# POWER2.net
KiCad netlist of a schematic drawn in Altium Designer
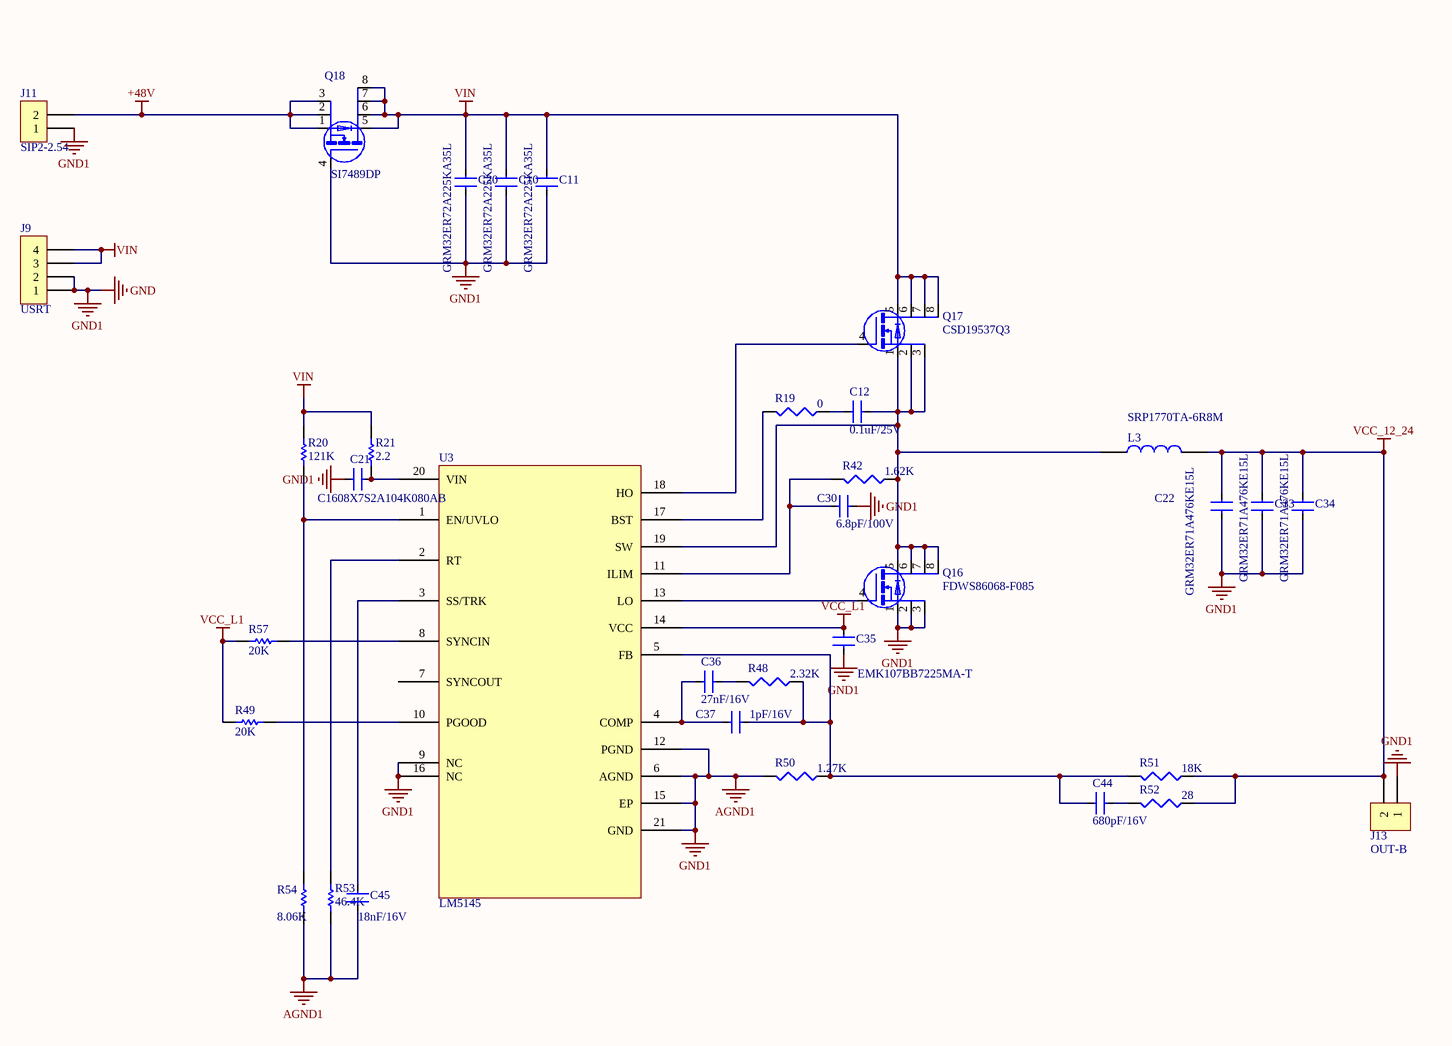
[diagram p0: POWER2.SchDoc]

(export (version "E")
  (design (tool "Eeschema 10.0.6"))
  (components
    (comp (ref "C10")
      (value "GRM32ER72A225KA35L")
      (footprint "1210C")
      (description "CCX85-103")
      (libsource (lib "无极性电容") (part "0.01UF"))
    )
    (comp (ref "C11")
      (value "GRM32ER72A225KA35L")
      (footprint "1210C")
      (description "CCX85-103")
      (libsource (lib "无极性电容") (part "0.01UF"))
    )
    (comp (ref "C12")
      (value "0.1uF/25V")
      (footprint "0603C")
      (description "CCX85-103")
      (libsource (lib "无极性电容") (part "0.01UF"))
    )
    (comp (ref "C20")
      (value "GRM32ER72A225KA35L")
      (footprint "1210C")
      (description "CCX85-103")
      (libsource (lib "无极性电容") (part "0.01UF"))
    )
    (comp (ref "C21")
      (value "C1608X7S2A104K080AB")
      (footprint "0603C")
      (description "CCX85-103")
      (libsource (lib "无极性电容") (part "0.01UF"))
    )
    (comp (ref "C22")
      (value "GRM32ER71A476KE15L")
      (footprint "1210C")
      (description "CCX85-103")
      (libsource (lib "无极性电容") (part "0.01UF"))
    )
    (comp (ref "C30")
      (value "6.8pF/100V")
      (footprint "0603C")
      (description "CCX85-103")
      (libsource (lib "无极性电容") (part "0.01UF"))
    )
    (comp (ref "C33")
      (value "GRM32ER71A476KE15L")
      (footprint "1210C")
      (description "CCX85-103")
      (libsource (lib "无极性电容") (part "0.01UF"))
    )
    (comp (ref "C34")
      (value "GRM32ER71A476KE15L")
      (footprint "1210C")
      (description "CCX85-103")
      (libsource (lib "无极性电容") (part "0.01UF"))
    )
    (comp (ref "C35")
      (value "EMK107BB7225MA-T")
      (footprint "0603C")
      (description "CCX85-103")
      (libsource (lib "无极性电容") (part "0.01UF"))
    )
    (comp (ref "C36")
      (value "27nF/16V")
      (footprint "0603C")
      (description "CCX85-103")
      (libsource (lib "无极性电容") (part "0.01UF"))
    )
    (comp (ref "C37")
      (value "1pF/16V")
      (footprint "0603C")
      (description "CCX85-103")
      (libsource (lib "无极性电容") (part "0.01UF"))
    )
    (comp (ref "C44")
      (value "680pF/16V")
      (footprint "0603C")
      (description "CCX85-103")
      (libsource (lib "无极性电容") (part "0.01UF"))
    )
    (comp (ref "C45")
      (value "18nF/16V")
      (footprint "0603C")
      (description "CCX85-103")
      (libsource (lib "无极性电容") (part "0.01UF"))
    )
    (comp (ref "J9")
      (value "USRT")
      (footprint "SIP-4L")
      (description "CN-SIP4-2.54")
      (libsource (lib "接插件") (part "SIP4-2.54"))
    )
    (comp (ref "J11")
      (value "SIP2-2.54")
      (footprint "CH3.96-2P")
      (description "CN-SIP2-2.54")
      (libsource (lib "接插件") (part "SIP2-2.54"))
    )
    (comp (ref "J13")
      (value "OUT-B")
      (footprint "CH3.96-2P")
      (description "Connector")
      (libsource (lib "SM") (part "CON2"))
    )
    (comp (ref "L3")
      (value "SRP1770TA-6R8M")
      (footprint "SRP1270-2R2M")
      (libsource (lib "*") (part "INDUCTOR"))
    )
    (comp (ref "Q16")
      (value "FDWS86068-F085")
      (footprint "PowerPAK SO-8")
      (description "Si4004DY")
      (libsource (lib "Schlib_20110825") (part "Si4004DY"))
    )
    (comp (ref "Q17")
      (value "CSD19537Q3")
      (footprint "PowerPAK SO-8")
      (description "Si4004DY")
      (libsource (lib "Schlib_20110825") (part "Si4004DY"))
    )
    (comp (ref "Q18")
      (value "SI7489DP")
      (footprint "PowerPAK SO-8")
      (description "Si4004DY")
      (libsource (lib "") (part "Si4004DY_1"))
    )
    (comp (ref "R19")
      (value "0")
      (footprint "0603R")
      (description "Resistor")
      (fields (field (name "PUBLISHER") "Altium Limited"))
      (libsource (lib "SM") (part "Res3"))
    )
    (comp (ref "R20")
      (value "121K")
      (footprint "0805R")
      (description "Semiconductor Resistor")
      (fields (field (name "PUBLISHER") "Altium Limited"))
      (libsource (lib "Miscellaneous Devices") (part "Res Semi"))
    )
    (comp (ref "R21")
      (value "2.2")
      (footprint "0603R")
      (description "Semiconductor Resistor")
      (fields (field (name "PUBLISHER") "Altium Limited"))
      (libsource (lib "Miscellaneous Devices") (part "Res Semi"))
    )
    (comp (ref "R42")
      (value "1.62K")
      (footprint "0603R")
      (description "Resistor")
      (fields (field (name "PUBLISHER") "Altium Limited"))
      (libsource (lib "SM") (part "Res3"))
    )
    (comp (ref "R48")
      (value "2.32K")
      (footprint "0603R")
      (description "Resistor")
      (fields (field (name "PUBLISHER") "Altium Limited"))
      (libsource (lib "SM") (part "Res3"))
    )
    (comp (ref "R49")
      (value "20K")
      (footprint "0603R")
      (description "Semiconductor Resistor")
      (fields (field (name "PUBLISHER") "Altium Limited"))
      (libsource (lib "Miscellaneous Devices") (part "Res Semi"))
    )
    (comp (ref "R50")
      (value "1.27K")
      (footprint "0603R")
      (description "Resistor")
      (fields (field (name "PUBLISHER") "Altium Limited"))
      (libsource (lib "SM") (part "Res3"))
    )
    (comp (ref "R51")
      (value "18K")
      (footprint "0603R")
      (description "Resistor")
      (fields (field (name "PUBLISHER") "Altium Limited"))
      (libsource (lib "SM") (part "Res3"))
    )
    (comp (ref "R52")
      (value "28")
      (footprint "0603R")
      (description "Resistor")
      (fields (field (name "PUBLISHER") "Altium Limited"))
      (libsource (lib "SM") (part "Res3"))
    )
    (comp (ref "R53")
      (value "46.4K")
      (footprint "0603R")
      (description "Semiconductor Resistor")
      (fields (field (name "PUBLISHER") "Altium Limited"))
      (libsource (lib "Miscellaneous Devices") (part "Res Semi"))
    )
    (comp (ref "R54")
      (value "8.06K")
      (footprint "0603R")
      (description "Semiconductor Resistor")
      (fields (field (name "PUBLISHER") "Altium Limited"))
      (libsource (lib "Miscellaneous Devices") (part "Res Semi"))
    )
    (comp (ref "R57")
      (value "20K")
      (footprint "0603R")
      (description "Semiconductor Resistor")
      (fields (field (name "PUBLISHER") "Altium Limited"))
      (libsource (lib "Miscellaneous Devices") (part "Res Semi"))
    )
    (comp (ref "U3")
      (value "LM5145")
      (footprint "QFN050P600-8N")
      (libsource (lib "Schlib_20110825") (part "LM5145"))
    )
  )
  (nets
    (net (code "1") (name "+48V") (class "Default")
      (node (ref "J11") (pin "2") (pinfunction "2_2") (pintype "passive"))
      (node (ref "Q18") (pin "1") (pinfunction "S_1") (pintype "passive"))
      (node (ref "Q18") (pin "2") (pinfunction "S_2") (pintype "passive"))
      (node (ref "Q18") (pin "3") (pinfunction "S_3") (pintype "passive"))
    )
    (net (code "2") (name "AGND1") (class "Default")
      (node (ref "C10") (pin "2") (pinfunction "2_2") (pintype "passive"))
      (node (ref "C11") (pin "2") (pinfunction "2_2") (pintype "passive"))
      (node (ref "C20") (pin "2") (pinfunction "2_2") (pintype "passive"))
      (node (ref "C21") (pin "1") (pinfunction "1_1") (pintype "passive"))
      (node (ref "C22") (pin "2") (pinfunction "2_2") (pintype "passive"))
      (node (ref "C30") (pin "1") (pinfunction "1_1") (pintype "passive"))
      (node (ref "C33") (pin "2") (pinfunction "2_2") (pintype "passive"))
      (node (ref "C34") (pin "2") (pinfunction "2_2") (pintype "passive"))
      (node (ref "C35") (pin "2") (pinfunction "2_2") (pintype "passive"))
      (node (ref "C45") (pin "2") (pinfunction "2_2") (pintype "passive"))
      (node (ref "J11") (pin "1") (pinfunction "1_1") (pintype "passive"))
      (node (ref "J13") (pin "1") (pinfunction "1_1") (pintype "passive"))
      (node (ref "J9") (pin "1") (pinfunction "1_1") (pintype "passive"))
      (node (ref "J9") (pin "2") (pinfunction "2_2") (pintype "passive"))
      (node (ref "Q16") (pin "1") (pinfunction "S_1") (pintype "passive"))
      (node (ref "Q16") (pin "2") (pinfunction "S_2") (pintype "passive"))
      (node (ref "Q16") (pin "3") (pinfunction "S_3") (pintype "passive"))
      (node (ref "Q18") (pin "4") (pinfunction "G_4") (pintype "passive"))
      (node (ref "R50") (pin "2") (pinfunction "2_2") (pintype "passive"))
      (node (ref "R53") (pin "1") (pinfunction "1_1") (pintype "passive"))
      (node (ref "R54") (pin "1") (pinfunction "1_1") (pintype "passive"))
      (node (ref "U3") (pin "12") (pinfunction "PGND_12") (pintype "passive"))
      (node (ref "U3") (pin "15") (pinfunction "EP_15") (pintype "passive"))
      (node (ref "U3") (pin "16") (pinfunction "NC_16") (pintype "passive"))
      (node (ref "U3") (pin "21") (pinfunction "GND_21") (pintype "passive"))
      (node (ref "U3") (pin "6") (pinfunction "AGND_6") (pintype "passive"))
      (node (ref "U3") (pin "9") (pinfunction "NC_9") (pintype "passive"))
    )
    (net (code "3") (name "Net-(C12-Pad1)") (class "Default")
      (node (ref "C12") (pin "1") (pinfunction "1_1") (pintype "passive"))
      (node (ref "R19") (pin "1") (pinfunction "1_1") (pintype "passive"))
    )
    (net (code "4") (name "Net-(C36-Pad2)") (class "Default")
      (node (ref "C36") (pin "2") (pinfunction "2_2") (pintype "passive"))
      (node (ref "R48") (pin "2") (pinfunction "2_2") (pintype "passive"))
    )
    (net (code "5") (name "Net-(C44-Pad2)") (class "Default")
      (node (ref "C44") (pin "2") (pinfunction "2_2") (pintype "passive"))
      (node (ref "R52") (pin "2") (pinfunction "2_2") (pintype "passive"))
    )
    (net (code "6") (name "Net-(Q16-G)") (class "Default")
      (node (ref "Q16") (pin "4") (pinfunction "G_4") (pintype "passive"))
      (node (ref "U3") (pin "13") (pinfunction "LO_13") (pintype "passive"))
    )
    (net (code "7") (name "Net-(Q17-G)") (class "Default")
      (node (ref "Q17") (pin "4") (pinfunction "G_4") (pintype "passive"))
      (node (ref "U3") (pin "18") (pinfunction "HO_18") (pintype "passive"))
    )
    (net (code "8") (name "Net-(U3-BST)") (class "Default")
      (node (ref "R19") (pin "2") (pinfunction "2_2") (pintype "passive"))
      (node (ref "U3") (pin "17") (pinfunction "BST_17") (pintype "passive"))
    )
    (net (code "9") (name "Net-(U3-COMP)") (class "Default")
      (node (ref "C36") (pin "1") (pinfunction "1_1") (pintype "passive"))
      (node (ref "C37") (pin "1") (pinfunction "1_1") (pintype "passive"))
      (node (ref "U3") (pin "4") (pinfunction "COMP_4") (pintype "passive"))
    )
    (net (code "10") (name "Net-(U3-EN{slash}UVLO)") (class "Default")
      (node (ref "R20") (pin "1") (pinfunction "1_1") (pintype "passive"))
      (node (ref "R54") (pin "2") (pinfunction "2_2") (pintype "passive"))
      (node (ref "U3") (pin "1") (pinfunction "EN/UVLO_1") (pintype "passive"))
    )
    (net (code "11") (name "Net-(U3-FB)") (class "Default")
      (node (ref "C37") (pin "2") (pinfunction "2_2") (pintype "passive"))
      (node (ref "C44") (pin "1") (pinfunction "1_1") (pintype "passive"))
      (node (ref "R48") (pin "1") (pinfunction "1_1") (pintype "passive"))
      (node (ref "R50") (pin "1") (pinfunction "1_1") (pintype "passive"))
      (node (ref "R51") (pin "2") (pinfunction "2_2") (pintype "passive"))
      (node (ref "U3") (pin "5") (pinfunction "FB_5") (pintype "passive"))
    )
    (net (code "12") (name "Net-(U3-ILIM)") (class "Default")
      (node (ref "C30") (pin "2") (pinfunction "2_2") (pintype "passive"))
      (node (ref "R42") (pin "2") (pinfunction "2_2") (pintype "passive"))
      (node (ref "U3") (pin "11") (pinfunction "ILIM_11") (pintype "passive"))
    )
    (net (code "13") (name "Net-(U3-PGOOD)") (class "Default")
      (node (ref "R49") (pin "1") (pinfunction "1_1") (pintype "passive"))
      (node (ref "U3") (pin "10") (pinfunction "PGOOD_10") (pintype "passive"))
    )
    (net (code "14") (name "Net-(U3-RT)") (class "Default")
      (node (ref "R53") (pin "2") (pinfunction "2_2") (pintype "passive"))
      (node (ref "U3") (pin "2") (pinfunction "RT_2") (pintype "passive"))
    )
    (net (code "15") (name "Net-(U3-SS{slash}TRK)") (class "Default")
      (node (ref "C45") (pin "1") (pinfunction "1_1") (pintype "passive"))
      (node (ref "U3") (pin "3") (pinfunction "SS/TRK_3") (pintype "passive"))
    )
    (net (code "16") (name "Net-(U3-SW)") (class "Default")
      (node (ref "C12") (pin "2") (pinfunction "2_2") (pintype "passive"))
      (node (ref "L3") (pin "1") (pinfunction "1_1") (pintype "passive"))
      (node (ref "Q16") (pin "5") (pinfunction "D_5") (pintype "passive"))
      (node (ref "Q16") (pin "6") (pinfunction "D_6") (pintype "passive"))
      (node (ref "Q16") (pin "7") (pinfunction "D_7") (pintype "passive"))
      (node (ref "Q16") (pin "8") (pinfunction "D_8") (pintype "passive"))
      (node (ref "Q17") (pin "1") (pinfunction "S_1") (pintype "passive"))
      (node (ref "Q17") (pin "2") (pinfunction "S_2") (pintype "passive"))
      (node (ref "Q17") (pin "3") (pinfunction "S_3") (pintype "passive"))
      (node (ref "R42") (pin "1") (pinfunction "1_1") (pintype "passive"))
      (node (ref "U3") (pin "19") (pinfunction "SW_19") (pintype "passive"))
    )
    (net (code "17") (name "Net-(U3-SYNCIN)") (class "Default")
      (node (ref "R57") (pin "1") (pinfunction "1_1") (pintype "passive"))
      (node (ref "U3") (pin "8") (pinfunction "SYNCIN_8") (pintype "passive"))
    )
    (net (code "18") (name "Net-(U3-VIN)") (class "Default")
      (node (ref "C21") (pin "2") (pinfunction "2_2") (pintype "passive"))
      (node (ref "R21") (pin "2") (pinfunction "2_2") (pintype "passive"))
      (node (ref "U3") (pin "20") (pinfunction "VIN_20") (pintype "passive"))
    )
    (net (code "19") (name "VCC_12_24") (class "Default")
      (node (ref "C22") (pin "1") (pinfunction "1_1") (pintype "passive"))
      (node (ref "C33") (pin "1") (pinfunction "1_1") (pintype "passive"))
      (node (ref "C34") (pin "1") (pinfunction "1_1") (pintype "passive"))
      (node (ref "J13") (pin "2") (pinfunction "2_2") (pintype "passive"))
      (node (ref "L3") (pin "2") (pinfunction "2_2") (pintype "passive"))
      (node (ref "R51") (pin "1") (pinfunction "1_1") (pintype "passive"))
      (node (ref "R52") (pin "1") (pinfunction "1_1") (pintype "passive"))
    )
    (net (code "20") (name "VCC_L1") (class "Default")
      (node (ref "C35") (pin "1") (pinfunction "1_1") (pintype "passive"))
      (node (ref "R49") (pin "2") (pinfunction "2_2") (pintype "passive"))
      (node (ref "R57") (pin "2") (pinfunction "2_2") (pintype "passive"))
      (node (ref "U3") (pin "14") (pinfunction "VCC_14") (pintype "passive"))
    )
    (net (code "21") (name "VIN") (class "Default")
      (node (ref "C10") (pin "1") (pinfunction "1_1") (pintype "passive"))
      (node (ref "C11") (pin "1") (pinfunction "1_1") (pintype "passive"))
      (node (ref "C20") (pin "1") (pinfunction "1_1") (pintype "passive"))
      (node (ref "J9") (pin "3") (pinfunction "3_3") (pintype "passive"))
      (node (ref "J9") (pin "4") (pinfunction "4_4") (pintype "passive"))
      (node (ref "Q17") (pin "5") (pinfunction "D_5") (pintype "passive"))
      (node (ref "Q17") (pin "6") (pinfunction "D_6") (pintype "passive"))
      (node (ref "Q17") (pin "7") (pinfunction "D_7") (pintype "passive"))
      (node (ref "Q17") (pin "8") (pinfunction "D_8") (pintype "passive"))
      (node (ref "Q18") (pin "5") (pinfunction "D_5") (pintype "passive"))
      (node (ref "Q18") (pin "6") (pinfunction "D_6") (pintype "passive"))
      (node (ref "Q18") (pin "7") (pinfunction "D_7") (pintype "passive"))
      (node (ref "Q18") (pin "8") (pinfunction "D_8") (pintype "passive"))
      (node (ref "R20") (pin "2") (pinfunction "2_2") (pintype "passive"))
      (node (ref "R21") (pin "1") (pinfunction "1_1") (pintype "passive"))
    )
    (net (code "22") (name "unconnected-(U3-SYNCOUT-Pad7)") (class "Default")
      (node (ref "U3") (pin "7") (pinfunction "SYNCOUT_7") (pintype "passive"))
    )
  )
)
